# olm-flora-sqw-RTC-thermistor-2inPVC.net
KiCad netlist of a schematic drawn in EAGLE
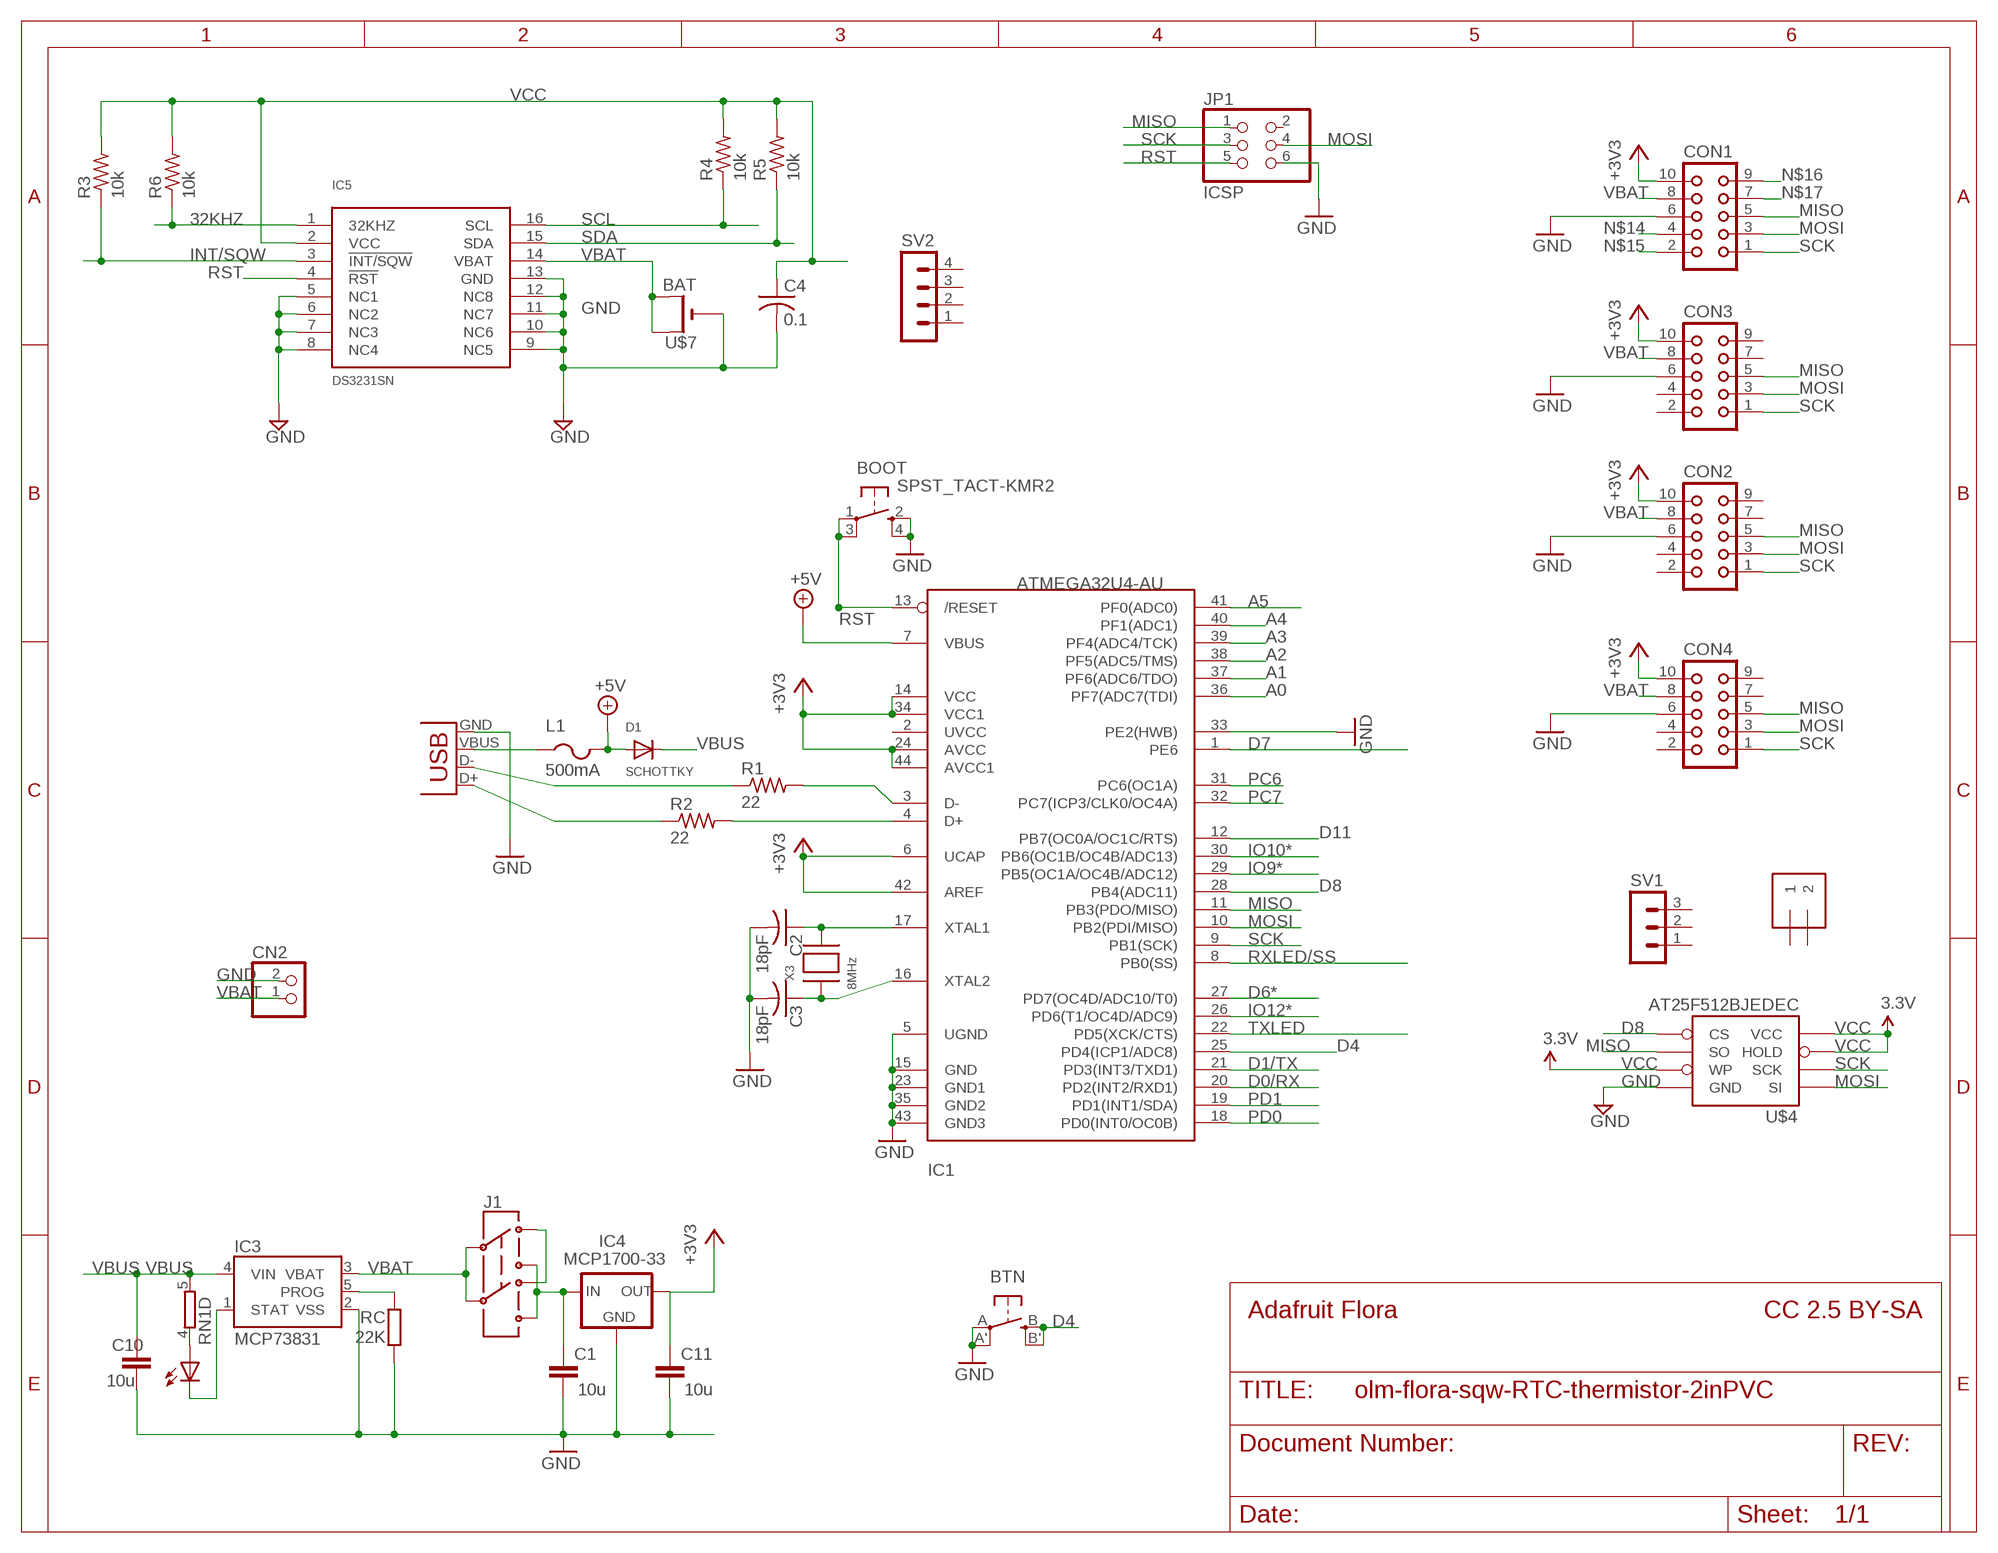
[diagram p0: schematic, sheet 1]

(export (version "E")
  (design (tool "Eeschema 10.0.6"))
  (components
    (comp (ref "BOOT")
      (value "SPST_TACT-KMR2")
      (footprint "eagle-import:KMR2")
      (libsource (lib "eagle-import") (part "SPST_TACT-KMR2"))
    )
    (comp (ref "BTN")
      (value "EVQQ2")
      (footprint "eagle-import:EVQ-Q2")
      (libsource (lib "eagle-import") (part "EVQQ2"))
    )
    (comp (ref "C1")
      (value "10u")
      (footprint "eagle-import:C0805")
      (libsource (lib "eagle-import") (part "C-EUC0805"))
    )
    (comp (ref "C2")
      (value "18pF")
      (footprint "eagle-import:C0805K")
      (libsource (lib "eagle-import") (part "C-USC0805K"))
    )
    (comp (ref "C3")
      (value "18pF")
      (footprint "eagle-import:C0805K")
      (libsource (lib "eagle-import") (part "C-USC0805K"))
    )
    (comp (ref "C4")
      (value "0.1")
      (footprint "eagle-import:C0805K")
      (libsource (lib "eagle-import") (part "C-USC0805K"))
    )
    (comp (ref "C10")
      (value "10u")
      (footprint "eagle-import:C0805")
      (libsource (lib "eagle-import") (part "C-EUC0805"))
    )
    (comp (ref "C11")
      (value "10u")
      (footprint "eagle-import:C0805")
      (libsource (lib "eagle-import") (part "C-EUC0805"))
    )
    (comp (ref "CHG")
      (value "0805")
      (footprint "eagle-import:CHIPLED_0805")
      (libsource (lib "eagle-import") (part "LEDCHIPLED_0805"))
    )
    (comp (ref "CN2")
      (value "JST_2PIN-SMT-RA")
      (footprint "eagle-import:JST-PH-2-SMT-RA")
      (libsource (lib "eagle-import") (part "JST_2PIN-SMT-RA"))
    )
    (comp (ref "CON1")
      (value "CON10")
      (footprint "eagle-import:CON10")
      (libsource (lib "eagle-import") (part "CON10"))
    )
    (comp (ref "CON2")
      (value "CON10")
      (footprint "eagle-import:CON10")
      (libsource (lib "eagle-import") (part "CON10"))
    )
    (comp (ref "CON3")
      (value "CON10")
      (footprint "eagle-import:CON10")
      (libsource (lib "eagle-import") (part "CON10"))
    )
    (comp (ref "CON4")
      (value "CON10")
      (footprint "eagle-import:CON10")
      (libsource (lib "eagle-import") (part "CON10"))
    )
    (comp (ref "D1")
      (value "SCHOTTKY")
      (footprint "eagle-import:SOD-123")
      (libsource (lib "eagle-import") (part "DIODESOD-123"))
    )
    (comp (ref "IC1")
      (value "ATMEGA32U4-AU")
      (footprint "eagle-import:TQFP44")
      (libsource (lib "eagle-import") (part "ATMEGA32U4-AU"))
    )
    (comp (ref "IC3")
      (value "MCP73831")
      (footprint "eagle-import:SOT23-5")
      (libsource (lib "eagle-import") (part "MCP73831"))
    )
    (comp (ref "IC4")
      (value "MCP1700-33")
      (footprint "eagle-import:SOT23")
      (libsource (lib "eagle-import") (part "MCP1700SOT233"))
    )
    (comp (ref "IC5")
      (value "DS3231SN")
      (footprint "eagle-import:SO16W")
      (libsource (lib "eagle-import") (part "DS3231SN"))
    )
    (comp (ref "J1")
      (value "AYZ0202")
      (footprint "eagle-import:AYZ0202")
      (libsource (lib "eagle-import") (part "AYZ0202"))
    )
    (comp (ref "J2")
      (value "1X2-3.5MM")
      (footprint "eagle-import:1X2-3.5MM")
      (libsource (lib "eagle-import") (part "1X2-3.5MM"))
    )
    (comp (ref "JP1")
      (value "ICSP")
      (footprint "eagle-import:2X03")
      (libsource (lib "eagle-import") (part "PINHD-2X3"))
    )
    (comp (ref "L1")
      (value "500mA")
      (footprint "eagle-import:R1206")
      (libsource (lib "eagle-import") (part "PTCFUSE-1206"))
    )
    (comp (ref "R1")
      (value "22")
      (footprint "eagle-import:R0805")
      (libsource (lib "eagle-import") (part "R-US_R0805"))
    )
    (comp (ref "R2")
      (value "22")
      (footprint "eagle-import:R0805")
      (libsource (lib "eagle-import") (part "R-US_R0805"))
    )
    (comp (ref "R3")
      (value "10k")
      (footprint "eagle-import:R0805")
      (libsource (lib "eagle-import") (part "R-US_R0805"))
    )
    (comp (ref "R4")
      (value "10k")
      (footprint "eagle-import:R0805")
      (libsource (lib "eagle-import") (part "R-US_R0805"))
    )
    (comp (ref "R5")
      (value "10k")
      (footprint "eagle-import:R0805")
      (libsource (lib "eagle-import") (part "R-US_R0805"))
    )
    (comp (ref "R6")
      (value "10k")
      (footprint "eagle-import:R0805")
      (libsource (lib "eagle-import") (part "R-US_R0805"))
    )
    (comp (ref "RC")
      (value "22K")
      (footprint "eagle-import:R0805")
      (libsource (lib "eagle-import") (part "R-EU_R0805"))
    )
    (comp (ref "RN1")
      (value "4R-NEXB38V")
      (footprint "eagle-import:EXB38V")
      (libsource (lib "eagle-import") (part "4R-NEXB38V"))
    )
    (comp (ref "SV1")
      (value "MA03-1")
      (footprint "eagle-import:MA03-1")
      (libsource (lib "eagle-import") (part "MA03-1"))
    )
    (comp (ref "SV2")
      (value "MA04-1")
      (footprint "eagle-import:MA04-1")
      (libsource (lib "eagle-import") (part "MA04-1"))
    )
    (comp (ref "U$4")
      (value "AT25F512BJEDEC")
      (footprint "eagle-import:SO08")
      (libsource (lib "eagle-import") (part "AT25F512BJEDEC"))
    )
    (comp (ref "U$7")
      (value "BAT")
      (footprint "eagle-import:CR1220-SMD")
      (libsource (lib "eagle-import") (part "CR1220SMT"))
    )
    (comp (ref "X1")
      (value "USBSMD")
      (footprint "eagle-import:USB-MINIB")
      (libsource (lib "eagle-import") (part "USBSMD"))
    )
    (comp (ref "X3")
      (value "8MHz")
      (footprint "eagle-import:NX5032")
      (libsource (lib "eagle-import") (part "XTALNX5032"))
    )
  )
  (nets
    (net (code "1") (name "+3V3") (class "Default")
      (node (ref "C11") (pin "1") (pinfunction "1_1") (pintype "passive"))
      (node (ref "CON1") (pin "10") (pinfunction "10_10") (pintype "passive"))
      (node (ref "CON2") (pin "10") (pinfunction "10_10") (pintype "passive"))
      (node (ref "CON3") (pin "10") (pinfunction "10_10") (pintype "passive"))
      (node (ref "CON4") (pin "10") (pinfunction "10_10") (pintype "passive"))
      (node (ref "IC1") (pin "14") (pinfunction "VCC_14") (pintype "bidirectional"))
      (node (ref "IC1") (pin "24") (pinfunction "AVCC_24") (pintype "bidirectional"))
      (node (ref "IC1") (pin "34") (pinfunction "VCC1_34") (pintype "bidirectional"))
      (node (ref "IC1") (pin "42") (pinfunction "AREF_42") (pintype "bidirectional"))
      (node (ref "IC1") (pin "44") (pinfunction "AVCC1_44") (pintype "bidirectional"))
      (node (ref "IC1") (pin "6") (pinfunction "UCAP_6") (pintype "bidirectional"))
      (node (ref "IC4") (pin "2") (pinfunction "OUT_2") (pintype "passive"))
    )
    (net (code "2") (name "+5V") (class "Default")
      (node (ref "D1") (pin "A") (pinfunction "A_A") (pintype "passive"))
      (node (ref "IC1") (pin "7") (pinfunction "VBUS_7") (pintype "bidirectional"))
      (node (ref "L1") (pin "2") (pinfunction "2_2") (pintype "passive"))
    )
    (net (code "3") (name "/32KHZ") (class "Default")
      (node (ref "IC5") (pin "1") (pinfunction "32KHZ_1") (pintype "bidirectional"))
      (node (ref "R6") (pin "1") (pinfunction "1_1") (pintype "passive"))
    )
    (net (code "4") (name "/A0") (class "Default")
      (node (ref "IC1") (pin "36") (pinfunction "PF7(ADC7(TDI)_36") (pintype "bidirectional"))
    )
    (net (code "5") (name "/A1") (class "Default")
      (node (ref "IC1") (pin "37") (pinfunction "PF6(ADC6/TDO)_37") (pintype "bidirectional"))
    )
    (net (code "6") (name "/A2") (class "Default")
      (node (ref "IC1") (pin "38") (pinfunction "PF5(ADC5/TMS)_38") (pintype "bidirectional"))
    )
    (net (code "7") (name "/A3") (class "Default")
      (node (ref "IC1") (pin "39") (pinfunction "PF4(ADC4/TCK)_39") (pintype "bidirectional"))
    )
    (net (code "8") (name "/A4") (class "Default")
      (node (ref "IC1") (pin "40") (pinfunction "PF1(ADC1)_40") (pintype "bidirectional"))
    )
    (net (code "9") (name "/A5") (class "Default")
      (node (ref "IC1") (pin "41") (pinfunction "PF0(ADC0)_41") (pintype "bidirectional"))
    )
    (net (code "10") (name "/D0{slash}RX") (class "Default")
      (node (ref "IC1") (pin "20") (pinfunction "PD2(INT2/RXD1)_20") (pintype "bidirectional"))
    )
    (net (code "11") (name "/D1{slash}TX") (class "Default")
      (node (ref "IC1") (pin "21") (pinfunction "PD3(INT3/TXD1)_21") (pintype "bidirectional"))
    )
    (net (code "12") (name "/D4") (class "Default")
      (node (ref "BTN") (pin "B") (pinfunction "S_B") (pintype "passive"))
      (node (ref "BTN") (pin "B'") (pinfunction "S1_B'") (pintype "passive"))
      (node (ref "IC1") (pin "25") (pinfunction "PD4(ICP1/ADC8)_25") (pintype "bidirectional"))
    )
    (net (code "13") (name "/D6*") (class "Default")
      (node (ref "IC1") (pin "27") (pinfunction "PD7(OC4D/ADC10/T0)_27") (pintype "bidirectional"))
    )
    (net (code "14") (name "/D7") (class "Default")
      (node (ref "IC1") (pin "1") (pinfunction "PE6_1") (pintype "bidirectional"))
    )
    (net (code "15") (name "/D8") (class "Default")
      (node (ref "IC1") (pin "28") (pinfunction "PB4(ADC11)_28") (pintype "bidirectional"))
      (node (ref "U$4") (pin "1_CS") (pinfunction "CS_1_CS") (pintype "bidirectional"))
    )
    (net (code "16") (name "/D11") (class "Default")
      (node (ref "IC1") (pin "12") (pinfunction "PB7(OC0A/OC1C/RTS)_12") (pintype "bidirectional"))
    )
    (net (code "17") (name "/INT{slash}SQW") (class "Default")
      (node (ref "IC5") (pin "3") (pinfunction "~{INT/SQW}_3") (pintype "bidirectional"))
      (node (ref "R3") (pin "1") (pinfunction "1_1") (pintype "passive"))
    )
    (net (code "18") (name "/IO9*") (class "Default")
      (node (ref "IC1") (pin "29") (pinfunction "PB5(OC1A/OC4B/ADC12)_29") (pintype "bidirectional"))
    )
    (net (code "19") (name "/IO10*") (class "Default")
      (node (ref "IC1") (pin "30") (pinfunction "PB6(OC1B/OC4B/ADC13)_30") (pintype "bidirectional"))
    )
    (net (code "20") (name "/IO12*") (class "Default")
      (node (ref "IC1") (pin "26") (pinfunction "PD6(T1/OC4D/ADC9)_26") (pintype "bidirectional"))
    )
    (net (code "21") (name "/MISO") (class "Default")
      (node (ref "CON1") (pin "5") (pinfunction "5_5") (pintype "passive"))
      (node (ref "CON2") (pin "5") (pinfunction "5_5") (pintype "passive"))
      (node (ref "CON3") (pin "5") (pinfunction "5_5") (pintype "passive"))
      (node (ref "CON4") (pin "5") (pinfunction "5_5") (pintype "passive"))
      (node (ref "IC1") (pin "11") (pinfunction "PB3(PDO/MISO)_11") (pintype "bidirectional"))
      (node (ref "JP1") (pin "1") (pinfunction "1_1") (pintype "passive"))
      (node (ref "U$4") (pin "2_SO") (pinfunction "SO_2_SO") (pintype "bidirectional"))
    )
    (net (code "22") (name "/MOSI") (class "Default")
      (node (ref "CON1") (pin "3") (pinfunction "3_3") (pintype "passive"))
      (node (ref "CON2") (pin "3") (pinfunction "3_3") (pintype "passive"))
      (node (ref "CON3") (pin "3") (pinfunction "3_3") (pintype "passive"))
      (node (ref "CON4") (pin "3") (pinfunction "3_3") (pintype "passive"))
      (node (ref "IC1") (pin "10") (pinfunction "PB2(PDI/MISO)_10") (pintype "bidirectional"))
      (node (ref "JP1") (pin "4") (pinfunction "4_4") (pintype "passive"))
      (node (ref "U$4") (pin "5_SI") (pinfunction "SI_5_SI") (pintype "bidirectional"))
    )
    (net (code "23") (name "/N$14") (class "Default")
      (node (ref "CON1") (pin "4") (pinfunction "4_4") (pintype "passive"))
    )
    (net (code "24") (name "/N$15") (class "Default")
      (node (ref "CON1") (pin "2") (pinfunction "2_2") (pintype "passive"))
    )
    (net (code "25") (name "/N$16") (class "Default")
      (node (ref "CON1") (pin "9") (pinfunction "9_9") (pintype "passive"))
    )
    (net (code "26") (name "/N$17") (class "Default")
      (node (ref "CON1") (pin "7") (pinfunction "7_7") (pintype "passive"))
    )
    (net (code "27") (name "/PC6") (class "Default")
      (node (ref "IC1") (pin "31") (pinfunction "PC6(OC1A)_31") (pintype "bidirectional"))
    )
    (net (code "28") (name "/PC7") (class "Default")
      (node (ref "IC1") (pin "32") (pinfunction "PC7(ICP3/CLK0/OC4A)_32") (pintype "bidirectional"))
    )
    (net (code "29") (name "/PD0") (class "Default")
      (node (ref "IC1") (pin "18") (pinfunction "PD0(INT0/OC0B)_18") (pintype "bidirectional"))
    )
    (net (code "30") (name "/PD1") (class "Default")
      (node (ref "IC1") (pin "19") (pinfunction "PD1(INT1/SDA)_19") (pintype "bidirectional"))
    )
    (net (code "31") (name "/RST") (class "Default")
      (node (ref "BOOT") (pin "1") (pinfunction "P_1") (pintype "passive"))
      (node (ref "BOOT") (pin "3") (pinfunction "P1_3") (pintype "passive"))
      (node (ref "IC1") (pin "13") (pinfunction "/RESET_13") (pintype "bidirectional"))
      (node (ref "IC5") (pin "4") (pinfunction "~{RST}_4") (pintype "bidirectional"))
      (node (ref "JP1") (pin "5") (pinfunction "5_5") (pintype "passive"))
    )
    (net (code "32") (name "/RXLED{slash}SS") (class "Default")
      (node (ref "IC1") (pin "8") (pinfunction "PB0(SS)_8") (pintype "bidirectional"))
    )
    (net (code "33") (name "/SCK") (class "Default")
      (node (ref "CON1") (pin "1") (pinfunction "1_1") (pintype "passive"))
      (node (ref "CON2") (pin "1") (pinfunction "1_1") (pintype "passive"))
      (node (ref "CON3") (pin "1") (pinfunction "1_1") (pintype "passive"))
      (node (ref "CON4") (pin "1") (pinfunction "1_1") (pintype "passive"))
      (node (ref "IC1") (pin "9") (pinfunction "PB1(SCK)_9") (pintype "bidirectional"))
      (node (ref "JP1") (pin "3") (pinfunction "3_3") (pintype "passive"))
      (node (ref "U$4") (pin "6_SCK") (pinfunction "SCK_6_SCK") (pintype "bidirectional"))
    )
    (net (code "34") (name "/SCL") (class "Default")
      (node (ref "IC5") (pin "16") (pinfunction "SCL_16") (pintype "bidirectional"))
      (node (ref "R4") (pin "1") (pinfunction "1_1") (pintype "passive"))
    )
    (net (code "35") (name "/SDA") (class "Default")
      (node (ref "IC5") (pin "15") (pinfunction "SDA_15") (pintype "bidirectional"))
      (node (ref "R5") (pin "1") (pinfunction "1_1") (pintype "passive"))
    )
    (net (code "36") (name "/TXLED") (class "Default")
      (node (ref "IC1") (pin "22") (pinfunction "PD5(XCK/CTS)_22") (pintype "bidirectional"))
    )
    (net (code "37") (name "/VBAT") (class "Default")
      (node (ref "CN2") (pin "1") (pinfunction "2_1") (pintype "passive"))
      (node (ref "CON1") (pin "8") (pinfunction "8_8") (pintype "passive"))
      (node (ref "CON2") (pin "8") (pinfunction "8_8") (pintype "passive"))
      (node (ref "CON3") (pin "8") (pinfunction "8_8") (pintype "passive"))
      (node (ref "CON4") (pin "8") (pinfunction "8_8") (pintype "passive"))
      (node (ref "IC3") (pin "3") (pinfunction "VBAT_3") (pintype "power_in"))
      (node (ref "IC5") (pin "14") (pinfunction "VBAT_14") (pintype "bidirectional"))
      (node (ref "J1") (pin "2") (pinfunction "2_2") (pintype "bidirectional"))
      (node (ref "J1") (pin "5") (pinfunction "5_5") (pintype "bidirectional"))
      (node (ref "U$7") (pin "+$1") (pinfunction "+_+$1") (pintype "passive"))
      (node (ref "U$7") (pin "+$2") (pinfunction "+1_+$2") (pintype "passive"))
    )
    (net (code "38") (name "/VBUS") (class "Default")
      (node (ref "C10") (pin "1") (pinfunction "1_1") (pintype "passive"))
      (node (ref "D1") (pin "C") (pinfunction "C_C") (pintype "passive"))
      (node (ref "IC3") (pin "4") (pinfunction "VIN_4") (pintype "power_in"))
      (node (ref "L1") (pin "1") (pinfunction "1_1") (pintype "passive"))
      (node (ref "RN1") (pin "5") (pinfunction "2_5") (pintype "passive"))
      (node (ref "X1") (pin "VBUS") (pinfunction "VBUS_VBUS") (pintype "bidirectional"))
    )
    (net (code "39") (name "3.3V") (class "Default")
      (node (ref "C4") (pin "1") (pinfunction "1_1") (pintype "passive"))
      (node (ref "IC5") (pin "2") (pinfunction "VCC_2") (pintype "bidirectional"))
      (node (ref "R3") (pin "2") (pinfunction "2_2") (pintype "passive"))
      (node (ref "R4") (pin "2") (pinfunction "2_2") (pintype "passive"))
      (node (ref "R5") (pin "2") (pinfunction "2_2") (pintype "passive"))
      (node (ref "R6") (pin "2") (pinfunction "2_2") (pintype "passive"))
      (node (ref "U$4") (pin "3_WP") (pinfunction "WP_3_WP") (pintype "bidirectional"))
      (node (ref "U$4") (pin "7_HOLD") (pinfunction "HOLD_7_HOLD") (pintype "bidirectional"))
      (node (ref "U$4") (pin "8_VCC") (pinfunction "VCC_8_VCC") (pintype "bidirectional"))
    )
    (net (code "40") (name "GND") (class "Default")
      (node (ref "BOOT") (pin "2") (pinfunction "S_2") (pintype "passive"))
      (node (ref "BOOT") (pin "4") (pinfunction "S1_4") (pintype "passive"))
      (node (ref "BTN") (pin "A") (pinfunction "P_A") (pintype "passive"))
      (node (ref "BTN") (pin "A'") (pinfunction "P1_A'") (pintype "passive"))
      (node (ref "C1") (pin "2") (pinfunction "2_2") (pintype "passive"))
      (node (ref "C10") (pin "2") (pinfunction "2_2") (pintype "passive"))
      (node (ref "C11") (pin "2") (pinfunction "2_2") (pintype "passive"))
      (node (ref "C2") (pin "2") (pinfunction "2_2") (pintype "passive"))
      (node (ref "C3") (pin "2") (pinfunction "2_2") (pintype "passive"))
      (node (ref "C4") (pin "2") (pinfunction "2_2") (pintype "passive"))
      (node (ref "CN2") (pin "2") (pinfunction "1_2") (pintype "passive"))
      (node (ref "CON1") (pin "6") (pinfunction "6_6") (pintype "passive"))
      (node (ref "CON2") (pin "6") (pinfunction "6_6") (pintype "passive"))
      (node (ref "CON3") (pin "6") (pinfunction "6_6") (pintype "passive"))
      (node (ref "CON4") (pin "6") (pinfunction "6_6") (pintype "passive"))
      (node (ref "IC1") (pin "15") (pinfunction "GND_15") (pintype "bidirectional"))
      (node (ref "IC1") (pin "23") (pinfunction "GND1_23") (pintype "bidirectional"))
      (node (ref "IC1") (pin "33") (pinfunction "PE2(HWB)_33") (pintype "bidirectional"))
      (node (ref "IC1") (pin "35") (pinfunction "GND2_35") (pintype "bidirectional"))
      (node (ref "IC1") (pin "43") (pinfunction "GND3_43") (pintype "bidirectional"))
      (node (ref "IC1") (pin "5") (pinfunction "UGND_5") (pintype "bidirectional"))
      (node (ref "IC3") (pin "2") (pinfunction "VSS_2") (pintype "power_in"))
      (node (ref "IC4") (pin "1") (pinfunction "GND_1") (pintype "input"))
      (node (ref "IC5") (pin "10") (pinfunction "NC6_10") (pintype "bidirectional"))
      (node (ref "IC5") (pin "11") (pinfunction "NC7_11") (pintype "bidirectional"))
      (node (ref "IC5") (pin "12") (pinfunction "NC8_12") (pintype "bidirectional"))
      (node (ref "IC5") (pin "13") (pinfunction "GND_13") (pintype "bidirectional"))
      (node (ref "IC5") (pin "5") (pinfunction "NC1_5") (pintype "bidirectional"))
      (node (ref "IC5") (pin "6") (pinfunction "NC2_6") (pintype "bidirectional"))
      (node (ref "IC5") (pin "7") (pinfunction "NC3_7") (pintype "bidirectional"))
      (node (ref "IC5") (pin "8") (pinfunction "NC4_8") (pintype "bidirectional"))
      (node (ref "IC5") (pin "9") (pinfunction "NC5_9") (pintype "bidirectional"))
      (node (ref "JP1") (pin "6") (pinfunction "6_6") (pintype "passive"))
      (node (ref "RC") (pin "1") (pinfunction "1_1") (pintype "passive"))
      (node (ref "U$4") (pin "4_GND") (pinfunction "GND_4_GND") (pintype "bidirectional"))
      (node (ref "U$7") (pin "-") (pinfunction "-_-") (pintype "passive"))
      (node (ref "X1") (pin "GND") (pinfunction "GND_GND") (pintype "bidirectional"))
    )
    (net (code "41") (name "Net-(IC1-D+)") (class "Default")
      (node (ref "IC1") (pin "4") (pinfunction "D+_4") (pintype "bidirectional"))
      (node (ref "R2") (pin "2") (pinfunction "2_2") (pintype "passive"))
    )
    (net (code "42") (name "Net-(IC1-D-)") (class "Default")
      (node (ref "IC1") (pin "3") (pinfunction "D-_3") (pintype "bidirectional"))
      (node (ref "R1") (pin "2") (pinfunction "2_2") (pintype "passive"))
    )
    (net (code "43") (name "Net-(IC1-XTAL1)") (class "Default")
      (node (ref "C2") (pin "1") (pinfunction "1_1") (pintype "passive"))
      (node (ref "IC1") (pin "17") (pinfunction "XTAL1_17") (pintype "bidirectional"))
      (node (ref "X3") (pin "P$2") (pinfunction "P$2_P$2") (pintype "bidirectional"))
    )
    (net (code "44") (name "Net-(IC1-XTAL2)") (class "Default")
      (node (ref "C3") (pin "1") (pinfunction "1_1") (pintype "passive"))
      (node (ref "IC1") (pin "16") (pinfunction "XTAL2_16") (pintype "bidirectional"))
      (node (ref "X3") (pin "P$1") (pinfunction "P$1_P$1") (pintype "bidirectional"))
    )
    (net (code "45") (name "Net-(IC3-PROG)") (class "Default")
      (node (ref "IC3") (pin "5") (pinfunction "PROG_5") (pintype "input"))
      (node (ref "RC") (pin "2") (pinfunction "2_2") (pintype "passive"))
    )
    (net (code "46") (name "Net-(IC3-STAT)") (class "Default")
      (node (ref "CHG") (pin "C") (pinfunction "C_C") (pintype "passive"))
      (node (ref "IC3") (pin "1") (pinfunction "STAT_1") (pintype "output"))
    )
    (net (code "47") (name "Net-(IC4-IN)") (class "Default")
      (node (ref "C1") (pin "1") (pinfunction "1_1") (pintype "passive"))
      (node (ref "IC4") (pin "3") (pinfunction "IN_3") (pintype "input"))
      (node (ref "J1") (pin "1") (pinfunction "3_1") (pintype "bidirectional"))
      (node (ref "J1") (pin "4") (pinfunction "6_4") (pintype "bidirectional"))
    )
    (net (code "48") (name "Net-(J1-1)") (class "Default")
      (node (ref "J1") (pin "3") (pinfunction "1_3") (pintype "bidirectional"))
      (node (ref "J1") (pin "6") (pinfunction "4_6") (pintype "bidirectional"))
    )
    (net (code "49") (name "Net-(R1-Pad1)") (class "Default")
      (node (ref "R1") (pin "1") (pinfunction "1_1") (pintype "passive"))
      (node (ref "X1") (pin "D-") (pinfunction "D-_D-") (pintype "bidirectional"))
    )
    (net (code "50") (name "Net-(R2-Pad1)") (class "Default")
      (node (ref "R2") (pin "1") (pinfunction "1_1") (pintype "passive"))
      (node (ref "X1") (pin "D+") (pinfunction "D+_D+") (pintype "bidirectional"))
    )
    (net (code "51") (name "Net-(RN1D-1)") (class "Default")
      (node (ref "CHG") (pin "A") (pinfunction "A_A") (pintype "passive"))
      (node (ref "RN1") (pin "4") (pinfunction "1_4") (pintype "passive"))
    )
    (net (code "52") (name "unconnected-(CON2-Pad2)") (class "Default")
      (node (ref "CON2") (pin "2") (pinfunction "2_2") (pintype "passive"))
    )
    (net (code "53") (name "unconnected-(CON2-Pad4)") (class "Default")
      (node (ref "CON2") (pin "4") (pinfunction "4_4") (pintype "passive"))
    )
    (net (code "54") (name "unconnected-(CON2-Pad7)") (class "Default")
      (node (ref "CON2") (pin "7") (pinfunction "7_7") (pintype "passive"))
    )
    (net (code "55") (name "unconnected-(CON2-Pad9)") (class "Default")
      (node (ref "CON2") (pin "9") (pinfunction "9_9") (pintype "passive"))
    )
    (net (code "56") (name "unconnected-(CON3-Pad2)") (class "Default")
      (node (ref "CON3") (pin "2") (pinfunction "2_2") (pintype "passive"))
    )
    (net (code "57") (name "unconnected-(CON3-Pad4)") (class "Default")
      (node (ref "CON3") (pin "4") (pinfunction "4_4") (pintype "passive"))
    )
    (net (code "58") (name "unconnected-(CON3-Pad7)") (class "Default")
      (node (ref "CON3") (pin "7") (pinfunction "7_7") (pintype "passive"))
    )
    (net (code "59") (name "unconnected-(CON3-Pad9)") (class "Default")
      (node (ref "CON3") (pin "9") (pinfunction "9_9") (pintype "passive"))
    )
    (net (code "60") (name "unconnected-(CON4-Pad2)") (class "Default")
      (node (ref "CON4") (pin "2") (pinfunction "2_2") (pintype "passive"))
    )
    (net (code "61") (name "unconnected-(CON4-Pad4)") (class "Default")
      (node (ref "CON4") (pin "4") (pinfunction "4_4") (pintype "passive"))
    )
    (net (code "62") (name "unconnected-(CON4-Pad7)") (class "Default")
      (node (ref "CON4") (pin "7") (pinfunction "7_7") (pintype "passive"))
    )
    (net (code "63") (name "unconnected-(CON4-Pad9)") (class "Default")
      (node (ref "CON4") (pin "9") (pinfunction "9_9") (pintype "passive"))
    )
    (net (code "64") (name "unconnected-(IC1-UVCC-Pad2)") (class "Default")
      (node (ref "IC1") (pin "2") (pinfunction "UVCC_2") (pintype "bidirectional"))
    )
    (net (code "65") (name "unconnected-(J2-Pad1)") (class "Default")
      (node (ref "J2") (pin "1") (pinfunction "1_1") (pintype "passive"))
    )
    (net (code "66") (name "unconnected-(J2-Pad2)") (class "Default")
      (node (ref "J2") (pin "2") (pinfunction "2_2") (pintype "passive"))
    )
    (net (code "67") (name "unconnected-(JP1-Pad2)") (class "Default")
      (node (ref "JP1") (pin "2") (pinfunction "2_2") (pintype "passive"))
    )
    (net (code "68") (name "unconnected-(SV1-Pad1)") (class "Default")
      (node (ref "SV1") (pin "1") (pinfunction "1_1") (pintype "passive"))
    )
    (net (code "69") (name "unconnected-(SV1-Pad2)") (class "Default")
      (node (ref "SV1") (pin "2") (pinfunction "2_2") (pintype "passive"))
    )
    (net (code "70") (name "unconnected-(SV1-Pad3)") (class "Default")
      (node (ref "SV1") (pin "3") (pinfunction "3_3") (pintype "passive"))
    )
    (net (code "71") (name "unconnected-(SV2-Pad1)") (class "Default")
      (node (ref "SV2") (pin "1") (pinfunction "1_1") (pintype "passive"))
    )
    (net (code "72") (name "unconnected-(SV2-Pad2)") (class "Default")
      (node (ref "SV2") (pin "2") (pinfunction "2_2") (pintype "passive"))
    )
    (net (code "73") (name "unconnected-(SV2-Pad3)") (class "Default")
      (node (ref "SV2") (pin "3") (pinfunction "3_3") (pintype "passive"))
    )
    (net (code "74") (name "unconnected-(SV2-Pad4)") (class "Default")
      (node (ref "SV2") (pin "4") (pinfunction "4_4") (pintype "passive"))
    )
  )
)
